# GPS.net
KiCad netlist of a schematic drawn in Altium Designer
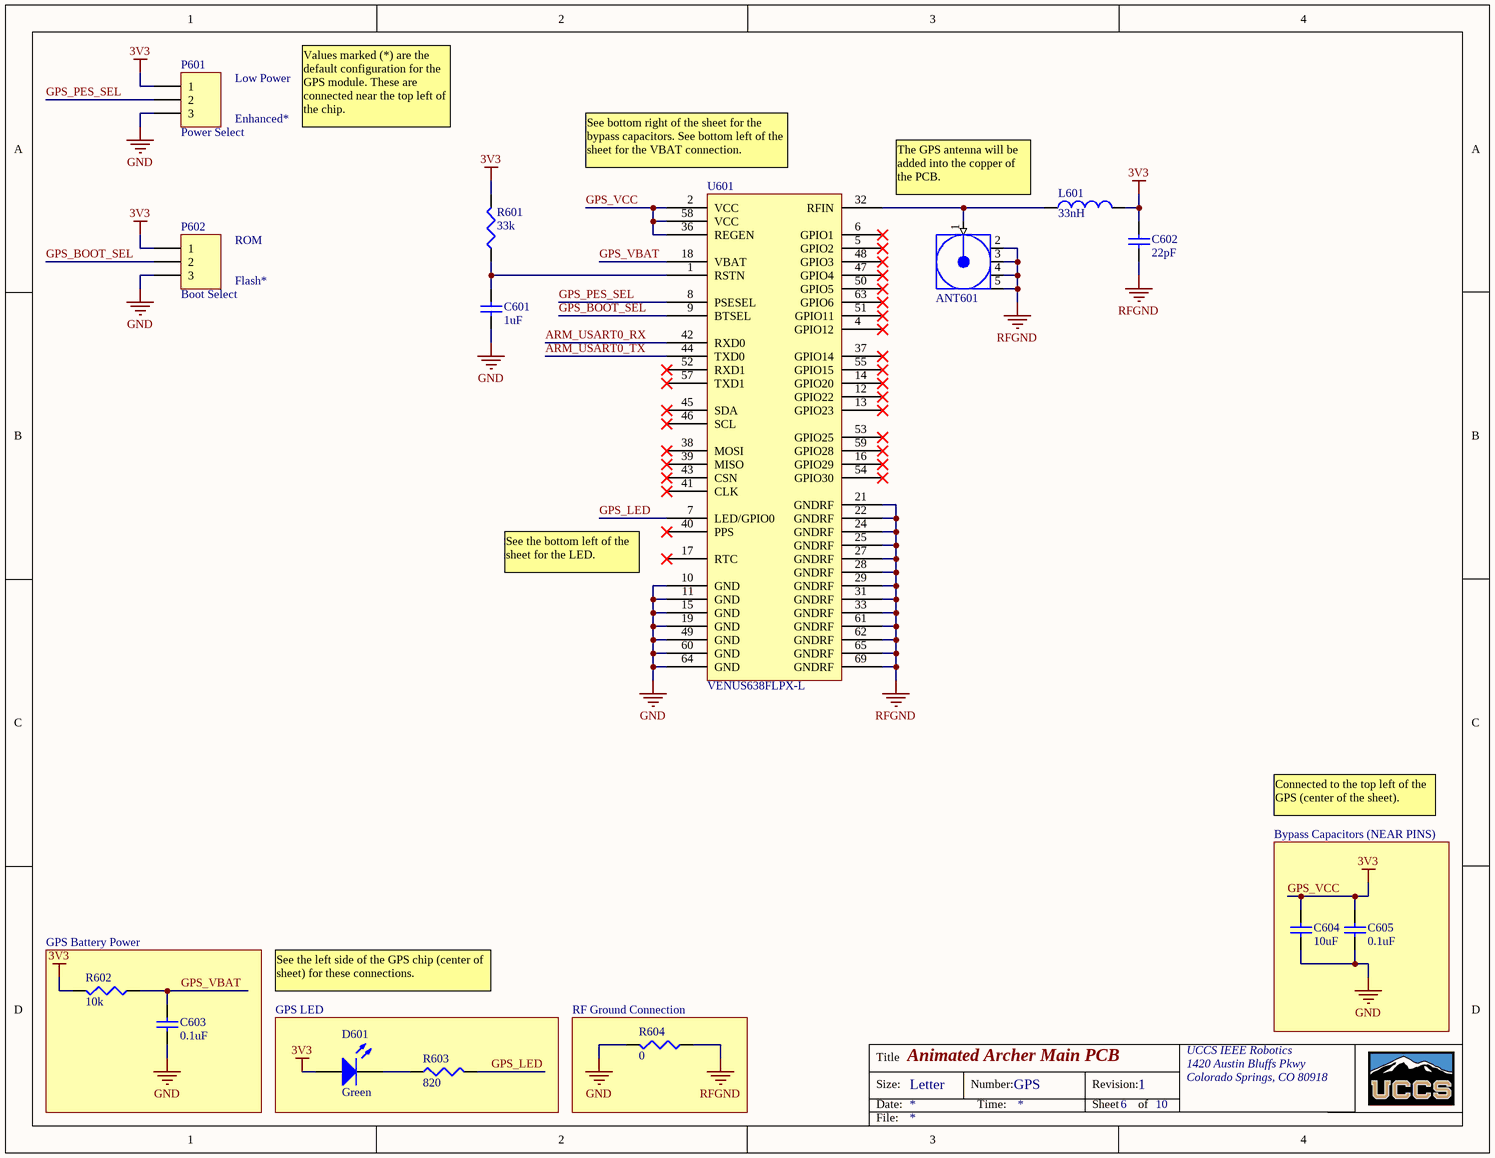
[diagram p0: GPS.SchDoc]

(export (version "E")
  (design (tool "Eeschema 10.0.6"))
  (components
    (comp (ref "ANT601")
      (value "COAX-M")
      (footprint "MMCX2.54-V5")
      (description "RF Coaxial PCB Connector, MMCX; Thru-Hole, Vertical Mount Plug,  50 Ohm Impedance")
      (fields (field (name "PUBLISHER") "Altium Limited"))
      (libsource (lib "Miscellaneous Connectors") (part "COAX-M"))
    )
    (comp (ref "C601")
      (value "1uF")
      (footprint "1608[0603]")
      (description "Capacitor (Semiconductor SIM Model)")
      (fields (field (name "Comment") "0.1uF") (field (name "PUBLISHER") "Altium Limited"))
      (libsource (lib "Miscellaneous Devices") (part "Cap Semi"))
    )
    (comp (ref "C602")
      (value "22pF")
      (footprint "1608[0603]")
      (description "Capacitor (Semiconductor SIM Model)")
      (fields (field (name "PUBLISHER") "Altium Limited"))
      (libsource (lib "Miscellaneous Devices") (part "Cap Semi"))
    )
    (comp (ref "C603")
      (value "0.1uF")
      (footprint "1608[0603]")
      (description "Capacitor (Semiconductor SIM Model)")
      (fields (field (name "PUBLISHER") "Altium Limited"))
      (libsource (lib "Miscellaneous Devices") (part "Cap Semi"))
    )
    (comp (ref "C604")
      (value "10uF")
      (footprint "1608[0603]")
      (description "Capacitor (Semiconductor SIM Model)")
      (fields (field (name "Comment") "0.1uF") (field (name "PUBLISHER") "Altium Limited"))
      (libsource (lib "Miscellaneous Devices") (part "Cap Semi"))
    )
    (comp (ref "C605")
      (value "0.1uF")
      (footprint "1608[0603]")
      (description "Capacitor (Semiconductor SIM Model)")
      (fields (field (name "PUBLISHER") "Altium Limited"))
      (libsource (lib "Miscellaneous Devices") (part "Cap Semi"))
    )
    (comp (ref "D601")
      (value "Green")
      (footprint "1608[0603]")
      (description "Typical RED, GREEN, YELLOW, AMBER GaAs LED")
      (fields (field (name "PUBLISHER") "Altium Limited"))
      (libsource (lib "Miscellaneous Devices") (part "LED2"))
    )
    (comp (ref "L601")
      (value "33nH")
      (footprint "0603")
      (description "Inductor")
      (fields (field (name "PUBLISHER") "Altium Limited"))
      (libsource (lib "Miscellaneous Devices") (part "Inductor"))
    )
    (comp (ref "P601")
      (value "Power Select")
      (footprint "HDR1X3")
      (description "Header, 3-Pin")
      (fields (field (name "PUBLISHER") "Altium Limited"))
      (libsource (lib "Miscellaneous Connectors") (part "Header 3"))
    )
    (comp (ref "P602")
      (value "Boot Select")
      (footprint "HDR1X3")
      (description "Header, 3-Pin")
      (fields (field (name "PUBLISHER") "Altium Limited"))
      (libsource (lib "Miscellaneous Connectors") (part "Header 3"))
    )
    (comp (ref "R601")
      (value "33k")
      (footprint "J1-0603")
      (description "Resistor")
      (fields (field (name "Comment") "Res3") (field (name "PUBLISHER") "Altium Limited"))
      (libsource (lib "Miscellaneous Devices") (part "Res3"))
    )
    (comp (ref "R602")
      (value "10k")
      (footprint "J1-0603")
      (description "Resistor")
      (fields (field (name "Comment") "Res3") (field (name "PUBLISHER") "Altium Limited"))
      (libsource (lib "Miscellaneous Devices") (part "Res3"))
    )
    (comp (ref "R603")
      (value "820")
      (footprint "J1-0603")
      (description "Resistor")
      (fields (field (name "Comment") "Res3") (field (name "PUBLISHER") "Altium Limited"))
      (libsource (lib "Miscellaneous Devices") (part "Res3"))
    )
    (comp (ref "R604")
      (value "0")
      (footprint "J1-0603")
      (description "Resistor")
      (fields (field (name "Comment") "Res3") (field (name "PUBLISHER") "Altium Limited"))
      (libsource (lib "Miscellaneous Devices") (part "Res3"))
    )
    (comp (ref "U601")
      (value "VENUS638FLPX-L")
      (footprint "VENUS638FLPX")
      (description "Venus638FLPX-L GPS Receiver")
      (libsource (lib "Animated Archer") (part "VENUS638FLPX-L"))
    )
  )
  (nets
    (net (code "1") (name "/ARM_USART0_RX") (class "Default")
      (node (ref "U601") (pin "42") (pinfunction "RXD0_42") (pintype "passive"))
    )
    (net (code "2") (name "/ARM_USART0_TX") (class "Default")
      (node (ref "U601") (pin "44") (pinfunction "TXD0_44") (pintype "passive"))
    )
    (net (code "3") (name "/GPS_BOOT_SEL") (class "Default")
      (node (ref "P602") (pin "2") (pinfunction "2_2") (pintype "passive"))
      (node (ref "U601") (pin "9") (pinfunction "BTSEL_9") (pintype "passive"))
    )
    (net (code "4") (name "/GPS_LED") (class "Default")
      (node (ref "R603") (pin "2") (pinfunction "2_2") (pintype "passive"))
      (node (ref "U601") (pin "7") (pinfunction "LED/GPIO0_7") (pintype "passive"))
    )
    (net (code "5") (name "/GPS_PES_SEL") (class "Default")
      (node (ref "P601") (pin "2") (pinfunction "2_2") (pintype "passive"))
      (node (ref "U601") (pin "8") (pinfunction "PSESEL_8") (pintype "passive"))
    )
    (net (code "6") (name "/GPS_VBAT") (class "Default")
      (node (ref "C603") (pin "2") (pinfunction "2_2") (pintype "passive"))
      (node (ref "R602") (pin "1") (pinfunction "1_1") (pintype "passive"))
      (node (ref "U601") (pin "18") (pinfunction "VBAT_18") (pintype "passive"))
    )
    (net (code "7") (name "3V3") (class "Default")
      (node (ref "C602") (pin "2") (pinfunction "2_2") (pintype "passive"))
      (node (ref "C604") (pin "2") (pinfunction "2_2") (pintype "passive"))
      (node (ref "C605") (pin "2") (pinfunction "2_2") (pintype "passive"))
      (node (ref "D601") (pin "1") (pinfunction "A_1") (pintype "passive"))
      (node (ref "L601") (pin "2") (pinfunction "2_2") (pintype "passive"))
      (node (ref "P601") (pin "1") (pinfunction "1_1") (pintype "passive"))
      (node (ref "P602") (pin "1") (pinfunction "1_1") (pintype "passive"))
      (node (ref "R601") (pin "2") (pinfunction "2_2") (pintype "passive"))
      (node (ref "R602") (pin "2") (pinfunction "2_2") (pintype "passive"))
      (node (ref "U601") (pin "2") (pinfunction "VCC_2") (pintype "passive"))
      (node (ref "U601") (pin "36") (pinfunction "REGEN_36") (pintype "passive"))
      (node (ref "U601") (pin "58") (pinfunction "VCC_58") (pintype "passive"))
    )
    (net (code "8") (name "GND") (class "Default")
      (node (ref "C601") (pin "1") (pinfunction "1_1") (pintype "passive"))
      (node (ref "C603") (pin "1") (pinfunction "1_1") (pintype "passive"))
      (node (ref "C604") (pin "1") (pinfunction "1_1") (pintype "passive"))
      (node (ref "C605") (pin "1") (pinfunction "1_1") (pintype "passive"))
      (node (ref "P601") (pin "3") (pinfunction "3_3") (pintype "passive"))
      (node (ref "P602") (pin "3") (pinfunction "3_3") (pintype "passive"))
      (node (ref "R604") (pin "2") (pinfunction "2_2") (pintype "passive"))
      (node (ref "U601") (pin "10") (pinfunction "GND_10") (pintype "passive"))
      (node (ref "U601") (pin "11") (pinfunction "GND_11") (pintype "passive"))
      (node (ref "U601") (pin "15") (pinfunction "GND_15") (pintype "passive"))
      (node (ref "U601") (pin "19") (pinfunction "GND_19") (pintype "passive"))
      (node (ref "U601") (pin "49") (pinfunction "GND_49") (pintype "passive"))
      (node (ref "U601") (pin "60") (pinfunction "GND_60") (pintype "passive"))
      (node (ref "U601") (pin "64") (pinfunction "GND_64") (pintype "passive"))
    )
    (net (code "9") (name "Net-(ANT601-Signal)") (class "Default")
      (node (ref "ANT601") (pin "1") (pinfunction "Signal_1") (pintype "input"))
      (node (ref "L601") (pin "1") (pinfunction "1_1") (pintype "passive"))
      (node (ref "U601") (pin "32") (pinfunction "RFIN_32") (pintype "passive"))
    )
    (net (code "10") (name "Net-(D601-K)") (class "Default")
      (node (ref "D601") (pin "2") (pinfunction "K_2") (pintype "passive"))
      (node (ref "R603") (pin "1") (pinfunction "1_1") (pintype "passive"))
    )
    (net (code "11") (name "Net-(U601-RSTN)") (class "Default")
      (node (ref "C601") (pin "2") (pinfunction "2_2") (pintype "passive"))
      (node (ref "R601") (pin "1") (pinfunction "1_1") (pintype "passive"))
      (node (ref "U601") (pin "1") (pinfunction "RSTN_1") (pintype "passive"))
    )
    (net (code "12") (name "RFGND") (class "Default")
      (node (ref "ANT601") (pin "2") (pinfunction "GND_2") (pintype "power_in"))
      (node (ref "ANT601") (pin "3") (pinfunction "GND_3") (pintype "power_in"))
      (node (ref "ANT601") (pin "4") (pinfunction "GND_4") (pintype "power_in"))
      (node (ref "ANT601") (pin "5") (pinfunction "GND_5") (pintype "power_in"))
      (node (ref "C602") (pin "1") (pinfunction "1_1") (pintype "passive"))
      (node (ref "R604") (pin "1") (pinfunction "1_1") (pintype "passive"))
      (node (ref "U601") (pin "21") (pinfunction "GNDRF_21") (pintype "passive"))
      (node (ref "U601") (pin "22") (pinfunction "GNDRF_22") (pintype "passive"))
      (node (ref "U601") (pin "24") (pinfunction "GNDRF_24") (pintype "passive"))
      (node (ref "U601") (pin "25") (pinfunction "GNDRF_25") (pintype "passive"))
      (node (ref "U601") (pin "27") (pinfunction "GNDRF_27") (pintype "passive"))
      (node (ref "U601") (pin "28") (pinfunction "GNDRF_28") (pintype "passive"))
      (node (ref "U601") (pin "29") (pinfunction "GNDRF_29") (pintype "passive"))
      (node (ref "U601") (pin "31") (pinfunction "GNDRF_31") (pintype "passive"))
      (node (ref "U601") (pin "33") (pinfunction "GNDRF_33") (pintype "passive"))
      (node (ref "U601") (pin "61") (pinfunction "GNDRF_61") (pintype "passive"))
      (node (ref "U601") (pin "62") (pinfunction "GNDRF_62") (pintype "passive"))
      (node (ref "U601") (pin "65") (pinfunction "GNDRF_65") (pintype "passive"))
      (node (ref "U601") (pin "69") (pinfunction "GNDRF_69") (pintype "passive"))
    )
    (net (code "13") (name "unconnected-(U601-CLK-Pad41)") (class "Default")
      (node (ref "U601") (pin "41") (pinfunction "CLK_41") (pintype "passive+no_connect"))
    )
    (net (code "14") (name "unconnected-(U601-CSN-Pad43)") (class "Default")
      (node (ref "U601") (pin "43") (pinfunction "CSN_43") (pintype "passive+no_connect"))
    )
    (net (code "15") (name "unconnected-(U601-GPIO1-Pad6)") (class "Default")
      (node (ref "U601") (pin "6") (pinfunction "GPIO1_6") (pintype "passive+no_connect"))
    )
    (net (code "16") (name "unconnected-(U601-GPIO2-Pad5)") (class "Default")
      (node (ref "U601") (pin "5") (pinfunction "GPIO2_5") (pintype "passive+no_connect"))
    )
    (net (code "17") (name "unconnected-(U601-GPIO3-Pad48)") (class "Default")
      (node (ref "U601") (pin "48") (pinfunction "GPIO3_48") (pintype "passive+no_connect"))
    )
    (net (code "18") (name "unconnected-(U601-GPIO4-Pad47)") (class "Default")
      (node (ref "U601") (pin "47") (pinfunction "GPIO4_47") (pintype "passive+no_connect"))
    )
    (net (code "19") (name "unconnected-(U601-GPIO5-Pad50)") (class "Default")
      (node (ref "U601") (pin "50") (pinfunction "GPIO5_50") (pintype "passive+no_connect"))
    )
    (net (code "20") (name "unconnected-(U601-GPIO6-Pad63)") (class "Default")
      (node (ref "U601") (pin "63") (pinfunction "GPIO6_63") (pintype "passive+no_connect"))
    )
    (net (code "21") (name "unconnected-(U601-GPIO11-Pad51)") (class "Default")
      (node (ref "U601") (pin "51") (pinfunction "GPIO11_51") (pintype "passive+no_connect"))
    )
    (net (code "22") (name "unconnected-(U601-GPIO12-Pad4)") (class "Default")
      (node (ref "U601") (pin "4") (pinfunction "GPIO12_4") (pintype "passive+no_connect"))
    )
    (net (code "23") (name "unconnected-(U601-GPIO14-Pad37)") (class "Default")
      (node (ref "U601") (pin "37") (pinfunction "GPIO14_37") (pintype "passive+no_connect"))
    )
    (net (code "24") (name "unconnected-(U601-GPIO15-Pad55)") (class "Default")
      (node (ref "U601") (pin "55") (pinfunction "GPIO15_55") (pintype "passive+no_connect"))
    )
    (net (code "25") (name "unconnected-(U601-GPIO20-Pad14)") (class "Default")
      (node (ref "U601") (pin "14") (pinfunction "GPIO20_14") (pintype "passive+no_connect"))
    )
    (net (code "26") (name "unconnected-(U601-GPIO22-Pad12)") (class "Default")
      (node (ref "U601") (pin "12") (pinfunction "GPIO22_12") (pintype "passive+no_connect"))
    )
    (net (code "27") (name "unconnected-(U601-GPIO23-Pad13)") (class "Default")
      (node (ref "U601") (pin "13") (pinfunction "GPIO23_13") (pintype "passive+no_connect"))
    )
    (net (code "28") (name "unconnected-(U601-GPIO25-Pad53)") (class "Default")
      (node (ref "U601") (pin "53") (pinfunction "GPIO25_53") (pintype "passive+no_connect"))
    )
    (net (code "29") (name "unconnected-(U601-GPIO28-Pad59)") (class "Default")
      (node (ref "U601") (pin "59") (pinfunction "GPIO28_59") (pintype "passive+no_connect"))
    )
    (net (code "30") (name "unconnected-(U601-GPIO29-Pad16)") (class "Default")
      (node (ref "U601") (pin "16") (pinfunction "GPIO29_16") (pintype "passive+no_connect"))
    )
    (net (code "31") (name "unconnected-(U601-GPIO30-Pad54)") (class "Default")
      (node (ref "U601") (pin "54") (pinfunction "GPIO30_54") (pintype "passive+no_connect"))
    )
    (net (code "32") (name "unconnected-(U601-MISO-Pad39)") (class "Default")
      (node (ref "U601") (pin "39") (pinfunction "MISO_39") (pintype "passive+no_connect"))
    )
    (net (code "33") (name "unconnected-(U601-MOSI-Pad38)") (class "Default")
      (node (ref "U601") (pin "38") (pinfunction "MOSI_38") (pintype "passive+no_connect"))
    )
    (net (code "34") (name "unconnected-(U601-PPS-Pad40)") (class "Default")
      (node (ref "U601") (pin "40") (pinfunction "PPS_40") (pintype "passive+no_connect"))
    )
    (net (code "35") (name "unconnected-(U601-RTC-Pad17)") (class "Default")
      (node (ref "U601") (pin "17") (pinfunction "RTC_17") (pintype "passive+no_connect"))
    )
    (net (code "36") (name "unconnected-(U601-RXD1-Pad52)") (class "Default")
      (node (ref "U601") (pin "52") (pinfunction "RXD1_52") (pintype "passive+no_connect"))
    )
    (net (code "37") (name "unconnected-(U601-SCL-Pad46)") (class "Default")
      (node (ref "U601") (pin "46") (pinfunction "SCL_46") (pintype "passive+no_connect"))
    )
    (net (code "38") (name "unconnected-(U601-SDA-Pad45)") (class "Default")
      (node (ref "U601") (pin "45") (pinfunction "SDA_45") (pintype "passive+no_connect"))
    )
    (net (code "39") (name "unconnected-(U601-TXD1-Pad57)") (class "Default")
      (node (ref "U601") (pin "57") (pinfunction "TXD1_57") (pintype "passive+no_connect"))
    )
  )
)
